# P-MT3620RDB-1-6_Dev.net
KiCad netlist of a schematic drawn in Altium Designer
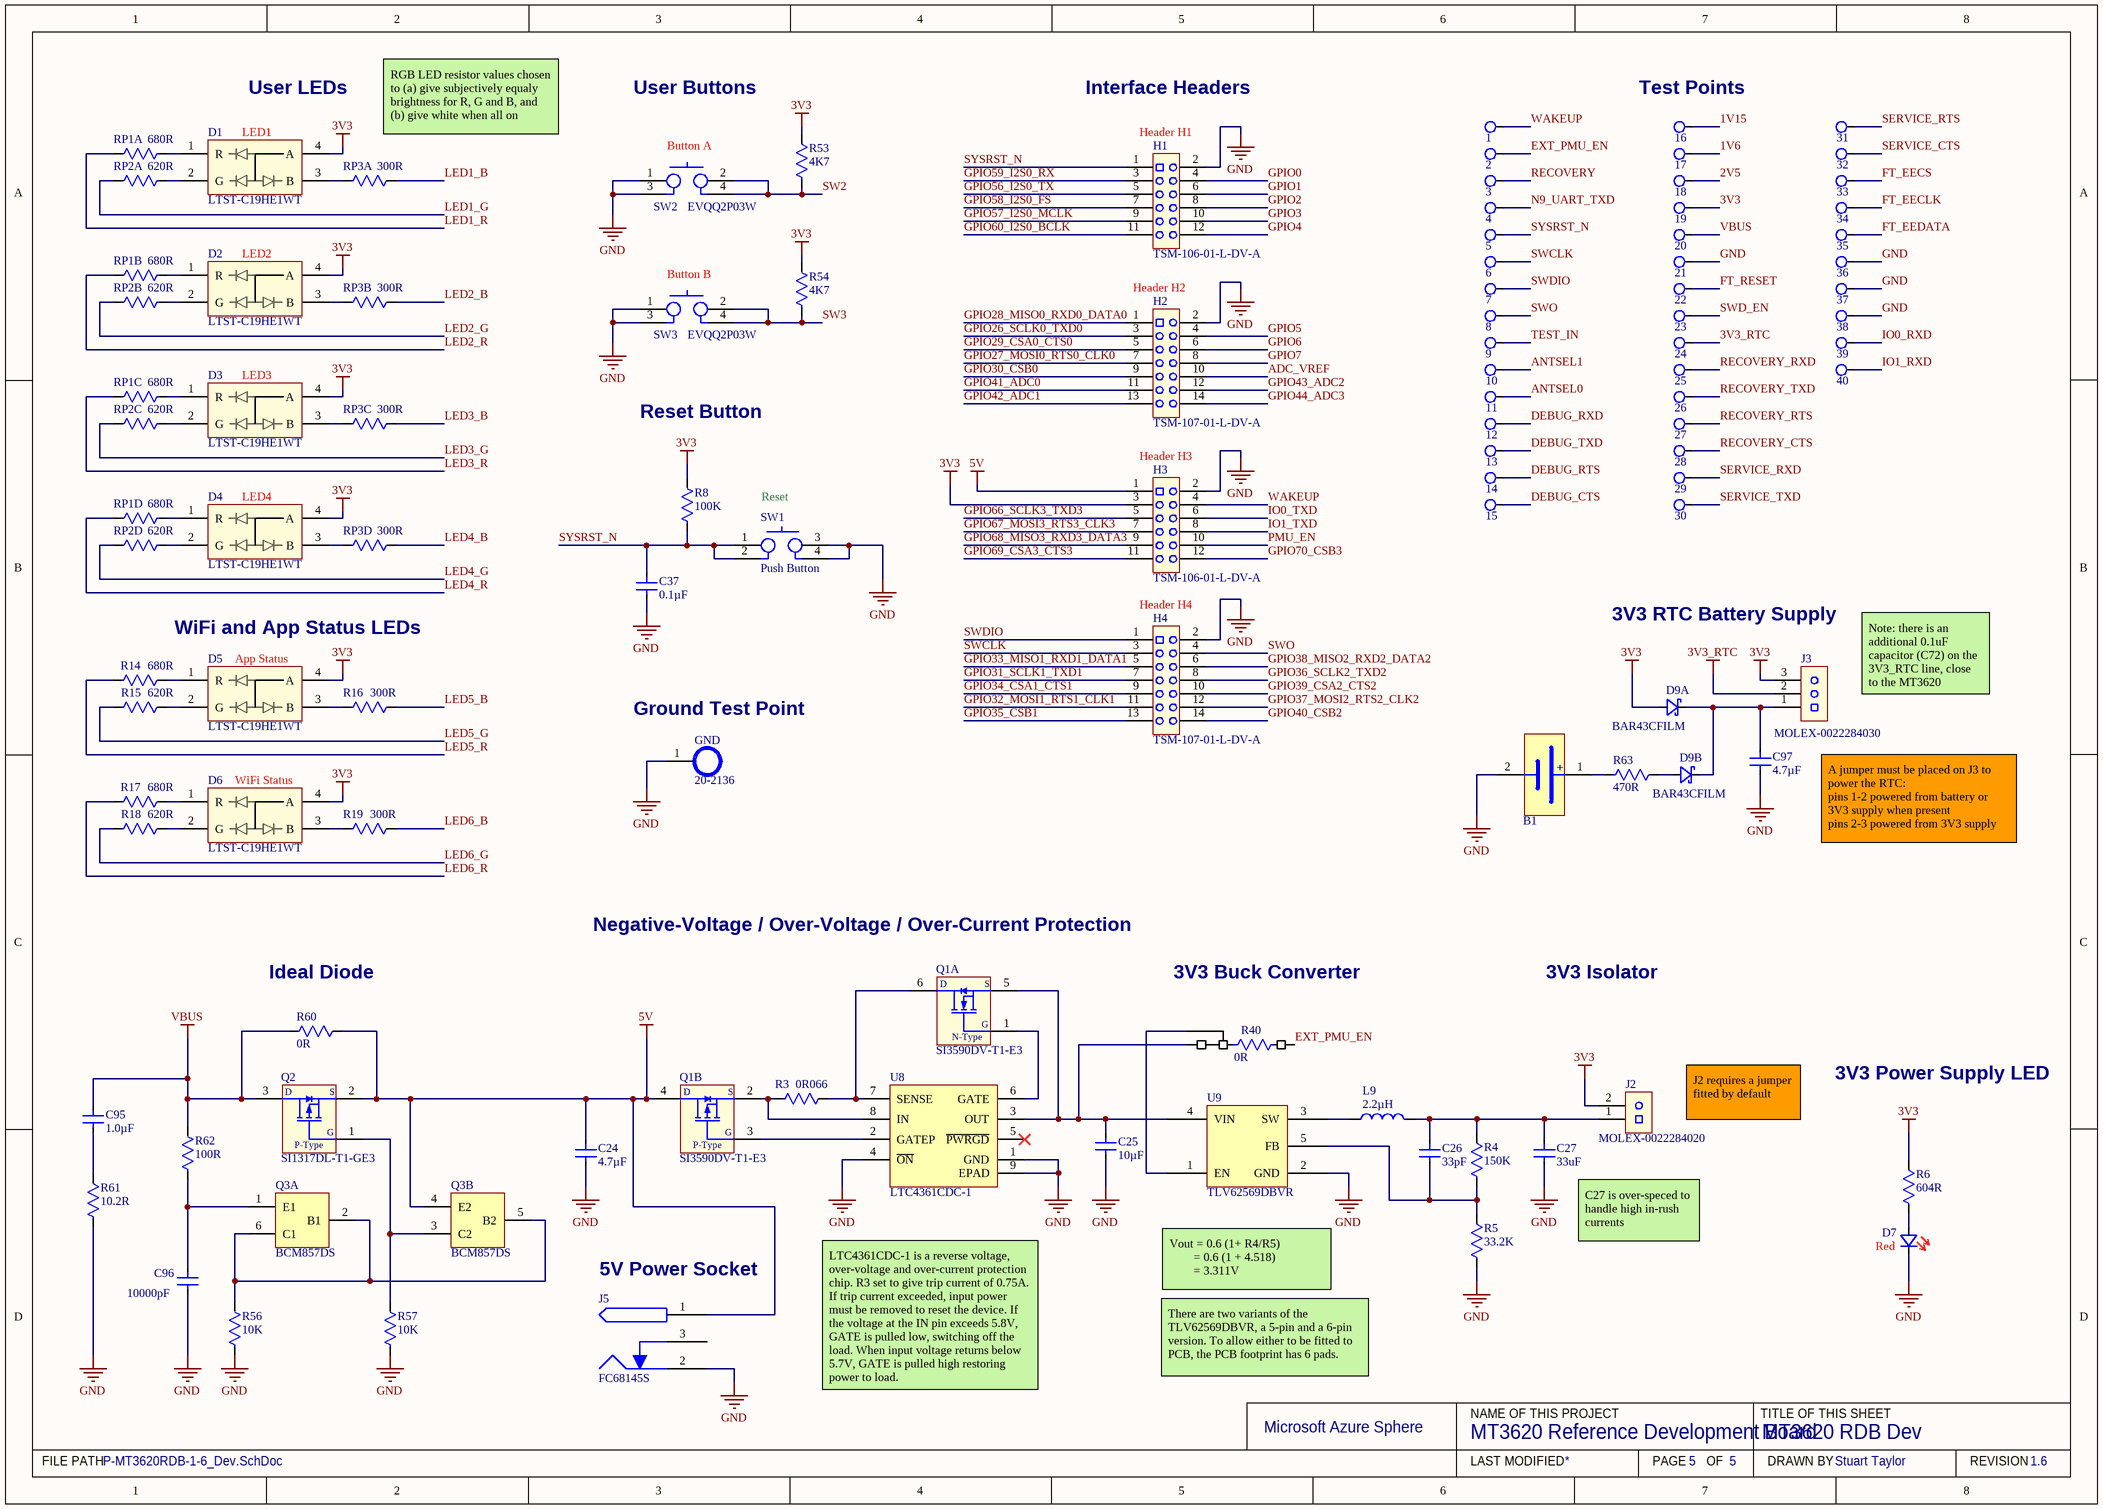
[diagram p0: P-MT3620RDB-1-6_Dev.SchDoc]

(export (version "E")
  (design (tool "Eeschema 10.0.6"))
  (components
    (comp (ref "1")
      (value "TestPoint")
      (footprint "Pad1.27mm")
      (description "Test Point")
      (libsource (lib "generic") (part "TestPoint"))
    )
    (comp (ref "2")
      (value "TestPoint")
      (footprint "Pad1.27mm")
      (description "Test Point")
      (libsource (lib "generic") (part "TestPoint"))
    )
    (comp (ref "3")
      (value "TestPoint")
      (footprint "Pad1.27mm")
      (description "Test Point")
      (libsource (lib "generic") (part "TestPoint"))
    )
    (comp (ref "4")
      (value "TestPoint")
      (footprint "Pad1.27mm")
      (description "Test Point")
      (libsource (lib "generic") (part "TestPoint"))
    )
    (comp (ref "5")
      (value "TestPoint")
      (footprint "Pad1.27mm")
      (description "Test Point")
      (libsource (lib "generic") (part "TestPoint"))
    )
    (comp (ref "6")
      (value "TestPoint")
      (footprint "Pad1.27mm")
      (description "Test Point")
      (libsource (lib "generic") (part "TestPoint"))
    )
    (comp (ref "7")
      (value "TestPoint")
      (footprint "Pad1.27mm")
      (description "Test Point")
      (libsource (lib "generic") (part "TestPoint"))
    )
    (comp (ref "8")
      (value "TestPoint")
      (footprint "Pad1.27mm")
      (description "Test Point")
      (libsource (lib "generic") (part "TestPoint"))
    )
    (comp (ref "9")
      (value "TestPoint")
      (footprint "Pad1.27mm")
      (description "Test Point")
      (libsource (lib "generic") (part "TestPoint"))
    )
    (comp (ref "10")
      (value "TestPoint")
      (footprint "Pad1.27mm")
      (description "Test Point")
      (libsource (lib "generic") (part "TestPoint"))
    )
    (comp (ref "11")
      (value "TestPoint")
      (footprint "Pad1.27mm")
      (description "Test Point")
      (libsource (lib "generic") (part "TestPoint"))
    )
    (comp (ref "12")
      (value "TestPoint")
      (footprint "Pad1.27mm")
      (description "Test Point")
      (libsource (lib "generic") (part "TestPoint"))
    )
    (comp (ref "13")
      (value "TestPoint")
      (footprint "Pad1.27mm")
      (description "Test Point")
      (libsource (lib "generic") (part "TestPoint"))
    )
    (comp (ref "14")
      (value "TestPoint")
      (footprint "Pad1.27mm")
      (description "Test Point")
      (libsource (lib "generic") (part "TestPoint"))
    )
    (comp (ref "15")
      (value "TestPoint")
      (footprint "Pad1.27mm")
      (description "Test Point")
      (libsource (lib "generic") (part "TestPoint"))
    )
    (comp (ref "16")
      (value "TestPoint")
      (footprint "Pad1.27mm")
      (description "Test Point")
      (libsource (lib "generic") (part "TestPoint"))
    )
    (comp (ref "17")
      (value "TestPoint")
      (footprint "Pad1.27mm")
      (description "Test Point")
      (libsource (lib "generic") (part "TestPoint"))
    )
    (comp (ref "18")
      (value "TestPoint")
      (footprint "Pad1.27mm")
      (description "Test Point")
      (libsource (lib "generic") (part "TestPoint"))
    )
    (comp (ref "19")
      (value "TestPoint")
      (footprint "Pad1.27mm")
      (description "Test Point")
      (libsource (lib "generic") (part "TestPoint"))
    )
    (comp (ref "20")
      (value "TestPoint")
      (footprint "Pad1.27mm")
      (description "Test Point")
      (libsource (lib "generic") (part "TestPoint"))
    )
    (comp (ref "21")
      (value "TestPoint")
      (footprint "Pad1.27mm")
      (description "Test Point")
      (libsource (lib "generic") (part "TestPoint"))
    )
    (comp (ref "22")
      (value "TestPoint")
      (footprint "Pad1.27mm")
      (description "Test Point")
      (libsource (lib "generic") (part "TestPoint"))
    )
    (comp (ref "23")
      (value "TestPoint")
      (footprint "Pad1.27mm")
      (description "Test Point")
      (libsource (lib "generic") (part "TestPoint"))
    )
    (comp (ref "24")
      (value "TestPoint")
      (footprint "Pad1.27mm")
      (description "Test Point")
      (libsource (lib "generic") (part "TestPoint"))
    )
    (comp (ref "25")
      (value "TestPoint")
      (footprint "Pad1.27mm")
      (description "Test Point")
      (libsource (lib "generic") (part "TestPoint"))
    )
    (comp (ref "26")
      (value "TestPoint")
      (footprint "Pad1.27mm")
      (description "Test Point")
      (libsource (lib "generic") (part "TestPoint"))
    )
    (comp (ref "27")
      (value "TestPoint")
      (footprint "Pad1.27mm")
      (description "Test Point")
      (libsource (lib "generic") (part "TestPoint"))
    )
    (comp (ref "28")
      (value "TestPoint")
      (footprint "Pad1.27mm")
      (description "Test Point")
      (libsource (lib "generic") (part "TestPoint"))
    )
    (comp (ref "29")
      (value "TestPoint")
      (footprint "Pad1.27mm")
      (description "Test Point")
      (libsource (lib "generic") (part "TestPoint"))
    )
    (comp (ref "30")
      (value "TestPoint")
      (footprint "Pad1.27mm")
      (description "Test Point")
      (libsource (lib "generic") (part "TestPoint"))
    )
    (comp (ref "31")
      (value "TestPoint")
      (footprint "Pad1.27mm")
      (description "Test Point")
      (libsource (lib "generic") (part "TestPoint"))
    )
    (comp (ref "32")
      (value "TestPoint")
      (footprint "Pad1.27mm")
      (description "Test Point")
      (libsource (lib "generic") (part "TestPoint"))
    )
    (comp (ref "33")
      (value "TestPoint")
      (footprint "Pad1.27mm")
      (description "Test Point")
      (libsource (lib "generic") (part "TestPoint"))
    )
    (comp (ref "34")
      (value "TestPoint")
      (footprint "Pad1.27mm")
      (description "Test Point")
      (libsource (lib "generic") (part "TestPoint"))
    )
    (comp (ref "35")
      (value "TestPoint")
      (footprint "Pad1.27mm")
      (description "Test Point")
      (libsource (lib "generic") (part "TestPoint"))
    )
    (comp (ref "36")
      (value "TestPoint")
      (footprint "Pad1.27mm")
      (description "Test Point")
      (libsource (lib "generic") (part "TestPoint"))
    )
    (comp (ref "37")
      (value "TestPoint")
      (footprint "Pad1.27mm")
      (description "Test Point")
      (libsource (lib "generic") (part "TestPoint"))
    )
    (comp (ref "38")
      (value "TestPoint")
      (footprint "Pad1.27mm")
      (description "Test Point")
      (libsource (lib "generic") (part "TestPoint"))
    )
    (comp (ref "39")
      (value "TestPoint")
      (footprint "Pad1.27mm")
      (description "Test Point")
      (libsource (lib "generic") (part "TestPoint"))
    )
    (comp (ref "40")
      (value "TestPoint")
      (footprint "Pad1.27mm")
      (description "Test Point")
      (libsource (lib "generic") (part "TestPoint"))
    )
    (comp (ref "B1")
      (value "HARWIN-S8421-45R")
      (footprint "HARWIN-S8421-45R")
      (description "SMT CR2032 coin cell holder")
      (fields (field (name "MANUFACTURER") "HARWIN") (field (name "MANUFACTURER PART NUMBER") "S8421-45R"))
      (libsource (lib "Harwin") (part "HARWIN-S8421-45R"))
    )
    (comp (ref "C24")
      (value "4.7µF")
      (footprint "CAPC1005-EIA0402 0.55MM MED")
      (description "CAP CER 4.7UF 10V 10% X5R 0402")
      (fields
        (field (name "MANUFACTURER") "TDK Corporation")
        (field (name "MANUFACTURER PART NUMBER") "C1005X5R1A475K050BC")
        (field (name "CAPACITANCE") "4.7µF")
      )
      (libsource (lib "TDK_Capacitor_C_0402") (part "4.7µF 0402 X5R 10V"))
    )
    (comp (ref "C25")
      (value "10µF")
      (footprint "CAPC1608-EIA0603-1MM-MED")
      (description "CAP CER 10UF 25V 20% X5R 0603")
      (fields
        (field (name "MANUFACTURER") "TDK Corporation")
        (field (name "MANUFACTURER PART NUMBER") "C1608X5R1E106M080AC")
        (field (name "CAPACITANCE") "10µF")
      )
      (libsource (lib "TDK-Capacitor_C_0603") (part "10µF 0603 X5R 25V"))
    )
    (comp (ref "C26")
      (value "33pF")
      (footprint "CAPC1005-EIA0402 0.55MM MED")
      (description "CAP CER 33PF 50V 5% NP0 0402")
      (fields
        (field (name "MANUFACTURER") "TDK Corporation")
        (field (name "MANUFACTURER PART NUMBER") "C1005C0G1H330J050BA")
        (field (name "CAPACITANCE") "33pF")
      )
      (libsource (lib "TDK_Capacitor_C_0402") (part "33pF 0402 C0G, NP0 50V"))
    )
    (comp (ref "C27")
      (value "33uF")
      (footprint "TDK_0805")
      (description "CAP CER 33UF 6.3V X5R 0805")
      (fields
        (field (name "MANUFACTURER") "TDK")
        (field (name "MANUFACTURER PART NUMBER") "C2012X5R0J336M125AC")
      )
      (libsource (lib "TDK_Capacitor_C_0805") (part "33uF 0805 X5R 6.3V"))
    )
    (comp (ref "C37")
      (value "0.1µF")
      (footprint "CAPC1005-EIA0402 0.55MM MED")
      (description "CAP CER 0.1UF 50V 10% X7R 0402")
      (fields
        (field (name "MANUFACTURER") "TDK Corporation")
        (field (name "MANUFACTURER PART NUMBER") "C1005X7R1H104K050BB")
        (field (name "CAPACITANCE") "0.1µF")
      )
      (libsource (lib "TDK_Capacitor_C_0402") (part "0.1µF 0402 X7R 50V"))
    )
    (comp (ref "C95")
      (value "1.0µF")
      (footprint "CAPC1005-EIA0402 0.55MM MED")
      (description "CAP CER 1UF 35V 10% X5R 0402")
      (fields
        (field (name "MANUFACTURER") "TDK Corporation")
        (field (name "MANUFACTURER PART NUMBER") "C1005X5R1V105K050BC")
        (field (name "CAPACITANCE") "1.0µF")
      )
      (libsource (lib "TDK_Capacitor_C_0402") (part "1.0µF 0402 X5R 35V"))
    )
    (comp (ref "C96")
      (value "10000pF")
      (footprint "CAPC1005-EIA0402 0.55MM MED")
      (description "CAP CER 10000PF 50V 10% X7R 0402")
      (fields
        (field (name "MANUFACTURER") "TDK Corporation")
        (field (name "MANUFACTURER PART NUMBER") "C1005X7R1H103K050BB")
        (field (name "CAPACITANCE") "10000pF")
      )
      (libsource (lib "TDK_Capacitor_C_0402") (part "10000pF 0402 X7R 50V"))
    )
    (comp (ref "C97")
      (value "4.7µF")
      (footprint "CAPC1005-EIA0402 0.55MM MED")
      (description "CAP CER 4.7UF 10V 10% X5R 0402")
      (fields
        (field (name "MANUFACTURER") "TDK Corporation")
        (field (name "MANUFACTURER PART NUMBER") "C1005X5R1A475K050BC")
        (field (name "CAPACITANCE") "4.7µF")
      )
      (libsource (lib "TDK_Capacitor_C_0402") (part "4.7µF 0402 X5R 10V"))
    )
    (comp (ref "D1")
      (value "LTST-C19HE1WT")
      (footprint "LTST-C19HE1WT")
      (description "LED RGB DIFFUSED 0606 SMD")
      (fields (field (name "MANUFACTURER") "Lite-On Inc."))
      (libsource (lib "Lite-On") (part "LTST-C19HE1WT"))
    )
    (comp (ref "D2")
      (value "LTST-C19HE1WT")
      (footprint "LTST-C19HE1WT")
      (description "LED RGB DIFFUSED 0606 SMD")
      (fields (field (name "MANUFACTURER") "Lite-On Inc."))
      (libsource (lib "Lite-On") (part "LTST-C19HE1WT"))
    )
    (comp (ref "D3")
      (value "LTST-C19HE1WT")
      (footprint "LTST-C19HE1WT")
      (description "LED RGB DIFFUSED 0606 SMD")
      (fields (field (name "MANUFACTURER") "Lite-On Inc."))
      (libsource (lib "Lite-On") (part "LTST-C19HE1WT"))
    )
    (comp (ref "D4")
      (value "LTST-C19HE1WT")
      (footprint "LTST-C19HE1WT")
      (description "LED RGB DIFFUSED 0606 SMD")
      (fields (field (name "MANUFACTURER") "Lite-On Inc."))
      (libsource (lib "Lite-On") (part "LTST-C19HE1WT"))
    )
    (comp (ref "D5")
      (value "LTST-C19HE1WT")
      (footprint "LTST-C19HE1WT")
      (description "LED RGB DIFFUSED 0606 SMD")
      (fields (field (name "MANUFACTURER") "Lite-On Inc."))
      (libsource (lib "Lite-On") (part "LTST-C19HE1WT"))
    )
    (comp (ref "D6")
      (value "LTST-C19HE1WT")
      (footprint "LTST-C19HE1WT")
      (description "LED RGB DIFFUSED 0606 SMD")
      (fields (field (name "MANUFACTURER") "Lite-On Inc."))
      (libsource (lib "Lite-On") (part "LTST-C19HE1WT"))
    )
    (comp (ref "D7")
      (value "Red LED")
      (footprint "Rohm SML-D12 Red")
      (description "1.6 x 0.8 x 0.55mm (0603) LED 620nm Red")
      (fields
        (field (name "MANUFACTURER") "Rohm Semiconductor")
        (field (name "MANUFACTURER PART NUMBER") "SML-D12U8WT86")
        (field (name "COLOUR") "Red")
      )
      (libsource (lib "Rohm") (part "SML-D12U"))
    )
    (comp (ref "D9")
      (value "BAR43CFILM")
      (footprint "ON_SEMI-SOT23-3")
      (description "DIODE ARRAY SCHOTTKY 30V SOT23-3")
      (fields (field (name "MANUFACTURER") "STMicroelectronics"))
      (libsource (lib "ST") (part "BAR43CFILM"))
    )
    (comp (ref "GND")
      (value "20-2136")
      (footprint "20-2136")
      (description "VERO - 20-2136 - TERMINAL, PCB, BLACK, PK100")
      (fields (field (name "MANUFACTURER") "VERO"))
      (libsource (lib "Vero") (part "20-2136"))
    )
    (comp (ref "H1")
      (value "TSM-106-01-L-DV-A")
      (footprint "TSM-106-01-L-DV-A")
      (description "CONN HEADER 12POS .100\" SMD GOLD")
      (fields (field (name "MANUFACTURER") "Samtec"))
      (libsource (lib "Samtec") (part "TSM-106-01-L-DV-A"))
    )
    (comp (ref "H2")
      (value "TSM-107-01-L-DV-A")
      (footprint "TSM-107-01-L-DV-A")
      (description "CONN HEADER 14POS .100\" SMD GOLD")
      (fields (field (name "MANUFACTURER") "Samtec"))
      (libsource (lib "Samtec") (part "TSM-107-01-L-DV-A"))
    )
    (comp (ref "H3")
      (value "TSM-106-01-L-DV-A")
      (footprint "TSM-106-01-L-DV-A")
      (description "CONN HEADER 12POS .100\" SMD GOLD")
      (fields (field (name "MANUFACTURER") "Samtec"))
      (libsource (lib "Samtec") (part "TSM-106-01-L-DV-A"))
    )
    (comp (ref "H4")
      (value "TSM-107-01-L-DV-A")
      (footprint "TSM-107-01-L-DV-A")
      (description "CONN HEADER 14POS .100\" SMD GOLD")
      (fields (field (name "MANUFACTURER") "Samtec"))
      (libsource (lib "Samtec") (part "TSM-107-01-L-DV-A"))
    )
    (comp (ref "J2")
      (value "MOLEX-0022284020")
      (footprint "0022284020")
      (description "CONN HEADER 2POS .100 VERT TIN")
      (fields
        (field (name "MANUFACTURER") "Molex, LLC")
        (field (name "MANUFACTURER PART NUMBER") "0022284020")
      )
      (libsource (lib "Molex") (part "MOLEX-0022284020"))
    )
    (comp (ref "J3")
      (value "MOLEX-0022284030")
      (footprint "0022284030")
      (description "CONN HEADER 3POS .100 VERT TIN")
      (fields
        (field (name "MANUFACTURER") "Molex, LLC")
        (field (name "MANUFACTURER PART NUMBER") "0022284030")
      )
      (libsource (lib "Molex") (part "MOLEX-0022284030"))
    )
    (comp (ref "J5")
      (value "FC68145S")
      (footprint "FC68145S")
      (description "CLIFF ELECTRONIC COMPONENTS, FC68145S, DC Power Connector, Jack, 1 A, 1.3 mm, Surface Mount")
      (fields (field (name "MANUFACTURER") "Cliff"))
      (libsource (lib "Cliff") (part "FC68145S"))
    )
    (comp (ref "L9")
      (value "2.2µH")
      (footprint "NR3015T2R2M")
      (description "FIXED IND 2.2UH 1.5A 72 MOHM SMD")
      (fields
        (field (name "MANUFACTURER") "Taiyo Yuden")
        (field (name "MANUFACTURER PART NUMBER") "NR3015T2R2M")
      )
      (libsource (lib "TaiyoYuden ") (part "NR3015T2R2M"))
    )
    (comp (ref "Q1")
      (value "SI3590DV-T1-E3")
      (footprint "SI3590DV-T1-E3")
      (description "MOSFET N&P-CH 30V (D-S)")
      (fields (field (name "MANUFACTURER") "Vishay Siliconix"))
      (libsource (lib "Vishay") (part "SI3590DV-T1-E3"))
    )
    (comp (ref "Q2")
      (value "SI1317DL-T1-GE3")
      (footprint "VISHAY_SOT-323")
      (description "VISHAY SI1317DL-T1-GE3 MOSFET Transistor, P Channel, -1.4 A, -20 V, 0.125 ohm, -4.5 V, 450 mV")
      (fields (field (name "MANUFACTURER") "Vishay Siliconix"))
      (libsource (lib "Vishay") (part "SI1317DL-T1-GE3"))
    )
    (comp (ref "Q3")
      (value "BCM857DS")
      (footprint "NXP-SOT457")
      (description "BJT ARRAY, DUAL PNP, -45V, -100MA, 6-SOT-457")
      (fields
        (field (name "MANUFACTURER") "NXP Semiconductors")
        (field (name "MANUFACTURER PART NUMBER") "BCM857DS,115")
      )
      (libsource (lib "NXP") (part "BCM857DS,115"))
    )
    (comp (ref "R3")
      (value "0R066")
      (footprint "VISHAY-0603")
      (description "Current Sense Resistors - SMD .4watt .066ohm 1%")
      (fields
        (field (name "MANUFACTURER") "Vishay Dale")
        (field (name "MANUFACTURER PART NUMBER") "WSLP0603R0660FEB")
      )
      (libsource (lib "Vishay") (part "WSLP0603R0660FEB"))
    )
    (comp (ref "R4")
      (value "150K")
      (footprint "RES 0402 MEDIUM DENSITY")
      (description "RES 150K OHM 1/10W 1% 0402 SMD")
      (fields
        (field (name "MANUFACTURER") "Panasonic Electronic Components")
        (field (name "MANUFACTURER PART NUMBER") "ERJ-2RKF1503X")
        (field (name "RESISTANCE (OHMS)") "150K")
      )
      (libsource (lib "Panasonic_Resistor_ERJ2R") (part "150K"))
    )
    (comp (ref "R5")
      (value "33.2K")
      (footprint "RES 0402 MEDIUM DENSITY")
      (description "RES 33.2K OHM 1/10W 1% 0402 SMD")
      (fields
        (field (name "MANUFACTURER") "Panasonic Electronic Components")
        (field (name "MANUFACTURER PART NUMBER") "ERJ-2RKF3322X")
        (field (name "RESISTANCE (OHMS)") "33.2K")
      )
      (libsource (lib "Panasonic_Resistor_ERJ2R") (part "33.2K"))
    )
    (comp (ref "R6")
      (value "604R")
      (footprint "RES 0402 MEDIUM DENSITY")
      (description "RES 604 OHM 1/10W 1% 0402 SMD")
      (fields
        (field (name "MANUFACTURER") "Panasonic Electronic Components")
        (field (name "MANUFACTURER PART NUMBER") "ERJ-2RKF6040X")
        (field (name "RESISTANCE (OHMS)") "604R")
      )
      (libsource (lib "Panasonic_Resistor_ERJ2R") (part "604R"))
    )
    (comp (ref "R8")
      (value "100K")
      (footprint "RES 0402 MEDIUM DENSITY")
      (description "RES 100K OHM 1/10W 1% 0402 SMD")
      (fields
        (field (name "MANUFACTURER") "Panasonic Electronic Components")
        (field (name "MANUFACTURER PART NUMBER") "ERJ-2RKF1003X")
        (field (name "RESISTANCE (OHMS)") "100K")
      )
      (libsource (lib "Panasonic_Resistor_ERJ2R") (part "100K"))
    )
    (comp (ref "R14")
      (value "680R")
      (footprint "RES 0402 MEDIUM DENSITY")
      (description "RES 680 OHM 1/10W 1% 0402 SMD")
      (fields
        (field (name "MANUFACTURER") "Panasonic Electronic Components")
        (field (name "MANUFACTURER PART NUMBER") "ERJ-2RKF6800X")
        (field (name "RESISTANCE (OHMS)") "680R")
      )
      (libsource (lib "Panasonic_Resistor_ERJ2R") (part "680R"))
    )
    (comp (ref "R15")
      (value "620R")
      (footprint "RES 0402 MEDIUM DENSITY")
      (description "RES 620 OHM 1/10W 1% 0402 SMD")
      (fields
        (field (name "MANUFACTURER") "Panasonic Electronic Components")
        (field (name "MANUFACTURER PART NUMBER") "ERJ-2RKF6200X")
        (field (name "RESISTANCE (OHMS)") "620R")
      )
      (libsource (lib "Panasonic_Resistor_ERJ2R") (part "620R"))
    )
    (comp (ref "R16")
      (value "300R")
      (footprint "RES 0402 MEDIUM DENSITY")
      (description "RES 300 OHM 1/10W 1% 0402 SMD")
      (fields
        (field (name "MANUFACTURER") "Panasonic Electronic Components")
        (field (name "MANUFACTURER PART NUMBER") "ERJ-2RKF3000X")
        (field (name "RESISTANCE (OHMS)") "300R")
      )
      (libsource (lib "Panasonic_Resistor_ERJ2R") (part "300R"))
    )
    (comp (ref "R17")
      (value "680R")
      (footprint "RES 0402 MEDIUM DENSITY")
      (description "RES 680 OHM 1/10W 1% 0402 SMD")
      (fields
        (field (name "MANUFACTURER") "Panasonic Electronic Components")
        (field (name "MANUFACTURER PART NUMBER") "ERJ-2RKF6800X")
        (field (name "RESISTANCE (OHMS)") "680R")
      )
      (libsource (lib "Panasonic_Resistor_ERJ2R") (part "680R"))
    )
    (comp (ref "R18")
      (value "620R")
      (footprint "RES 0402 MEDIUM DENSITY")
      (description "RES 620 OHM 1/10W 1% 0402 SMD")
      (fields
        (field (name "MANUFACTURER") "Panasonic Electronic Components")
        (field (name "MANUFACTURER PART NUMBER") "ERJ-2RKF6200X")
        (field (name "RESISTANCE (OHMS)") "620R")
      )
      (libsource (lib "Panasonic_Resistor_ERJ2R") (part "620R"))
    )
    (comp (ref "R19")
      (value "300R")
      (footprint "RES 0402 MEDIUM DENSITY")
      (description "RES 300 OHM 1/10W 1% 0402 SMD")
      (fields
        (field (name "MANUFACTURER") "Panasonic Electronic Components")
        (field (name "MANUFACTURER PART NUMBER") "ERJ-2RKF3000X")
        (field (name "RESISTANCE (OHMS)") "300R")
      )
      (libsource (lib "Panasonic_Resistor_ERJ2R") (part "300R"))
    )
    (comp (ref "R40")
      (value "0R")
      (footprint "THREE-WAY-0402-WITH-SHORT")
      (description "RES SMD 0.0OHM JUMPER 1/10W 0402")
      (fields
        (field (name "MANUFACTURER") "Panasonic Electronic Components")
        (field (name "MANUFACTURER PART NUMBER") "ERJ-2GE0R00X")
      )
      (libsource (lib "generic-res") (part "THREE-WAY-0R-0402"))
    )
    (comp (ref "R53")
      (value "4K7")
      (footprint "RES 0402 MEDIUM DENSITY")
      (description "RES 4.7K OHM 1/10W 1% 0402 SMD")
      (fields
        (field (name "MANUFACTURER") "Panasonic Electronic Components")
        (field (name "MANUFACTURER PART NUMBER") "ERJ-2RKF4701X")
        (field (name "RESISTANCE (OHMS)") "4K7")
      )
      (libsource (lib "Panasonic_Resistor_ERJ2R") (part "4.7K"))
    )
    (comp (ref "R54")
      (value "4K7")
      (footprint "RES 0402 MEDIUM DENSITY")
      (description "RES 4.7K OHM 1/10W 1% 0402 SMD")
      (fields
        (field (name "MANUFACTURER") "Panasonic Electronic Components")
        (field (name "MANUFACTURER PART NUMBER") "ERJ-2RKF4701X")
        (field (name "RESISTANCE (OHMS)") "4K7")
      )
      (libsource (lib "Panasonic_Resistor_ERJ2R") (part "4.7K"))
    )
    (comp (ref "R56")
      (value "10K")
      (footprint "RES 0402 MEDIUM DENSITY")
      (description "RES 10K OHM 1/10W 1% 0402 SMD")
      (fields
        (field (name "MANUFACTURER") "Panasonic Electronic Components")
        (field (name "MANUFACTURER PART NUMBER") "ERJ-2RKF1002X")
        (field (name "RESISTANCE (OHMS)") "10K")
      )
      (libsource (lib "Panasonic_Resistor_ERJ2R") (part "10K"))
    )
    (comp (ref "R57")
      (value "10K")
      (footprint "RES 0402 MEDIUM DENSITY")
      (description "RES 10K OHM 1/10W 1% 0402 SMD")
      (fields
        (field (name "MANUFACTURER") "Panasonic Electronic Components")
        (field (name "MANUFACTURER PART NUMBER") "ERJ-2RKF1002X")
        (field (name "RESISTANCE (OHMS)") "10K")
      )
      (libsource (lib "Panasonic_Resistor_ERJ2R") (part "10K"))
    )
    (comp (ref "R60")
      (value "0R")
      (footprint "RES 0402 MEDIUM DENSITY")
      (description "RES 0.0 OHM 1/10W JUMP 0402 SMD")
      (fields
        (field (name "MANUFACTURER") "Panasonic Electronic Components")
        (field (name "MANUFACTURER PART NUMBER") "ERJ-2GE0R00X")
        (field (name "RESISTANCE (OHMS)") "0R")
      )
      (libsource (lib "Panasonic_Resistor_ERJ2R") (part "0R"))
    )
    (comp (ref "R61")
      (value "10.2R")
      (footprint "RES 0402 MEDIUM DENSITY")
      (description "RES 10.2 OHM 1/10W 1% 0402 SMD")
      (fields
        (field (name "MANUFACTURER") "Panasonic Electronic Components")
        (field (name "MANUFACTURER PART NUMBER") "ERJ-2RKF10R2X")
        (field (name "RESISTANCE (OHMS)") "10.2R")
      )
      (libsource (lib "Panasonic_Resistor_ERJ2R") (part "10.2R"))
    )
    (comp (ref "R62")
      (value "100R")
      (footprint "RES 0402 MEDIUM DENSITY")
      (description "RES 100 OHM 1/10W 1% 0402 SMD")
      (fields
        (field (name "MANUFACTURER") "Panasonic Electronic Components")
        (field (name "MANUFACTURER PART NUMBER") "ERJ-2RKF1000X")
        (field (name "RESISTANCE (OHMS)") "100R")
      )
      (libsource (lib "Panasonic_Resistor_ERJ2R") (part "100R"))
    )
    (comp (ref "R63")
      (value "470R")
      (footprint "RES 0402 MEDIUM DENSITY")
      (description "RES 470 OHM 1/10W 1% 0402 SMD")
      (fields
        (field (name "MANUFACTURER") "Panasonic Electronic Components")
        (field (name "MANUFACTURER PART NUMBER") "ERJ-2RKF4700X")
        (field (name "RESISTANCE (OHMS)") "470R")
      )
      (libsource (lib "Panasonic_Resistor_ERJ2R") (part "470R"))
    )
    (comp (ref "RP1")
      (value "680R")
      (footprint "EXB-N8V")
      (fields
        (field (name "MANUFACTURER") "Panasonic / Panasonic ECG")
        (field (name "MANUFACTURER PART NUMBER") "EXB-N8V681JX")
      )
      (libsource (lib "Panasonic") (part "EXB-N8V681JX"))
    )
    (comp (ref "RP2")
      (value "620R")
      (footprint "EXB-N8V")
      (fields
        (field (name "MANUFACTURER") "Panasonic ECG")
        (field (name "MANUFACTURER PART NUMBER") "EXB-N8V621JX")
        (field (name "TOLERANCE") "5%")
      )
      (libsource (lib "Panasonic") (part "EXB-N8V621JX"))
    )
    (comp (ref "RP3")
      (value "300R")
      (footprint "EXB-N8V")
      (fields
        (field (name "MANUFACTURER") "Panasonic / Panasonic ECG")
        (field (name "MANUFACTURER PART NUMBER") "EXB-N8V301JX")
        (field (name "TOLERANCE") "5%")
      )
      (libsource (lib "Panasonic") (part "EXB-N8V301JX"))
    )
    (comp (ref "SW1")
      (value "Push Button")
      (footprint "DHT-1158")
      (libsource (lib "Seeed") (part "DHT-1158"))
    )
    (comp (ref "SW2")
      (value "SWI TACT SPN0 PANASONIC EVQQ2P03W")
      (footprint "EVQQ2P03W")
      (description "PANASONIC - EVQQ2P03W - SWITCH, SPNO, SMD")
      (fields (field (name "MANUFACTURER") "PANASONIC") (field (name "MANUFACTURER PART NUMBER") "EVQQ2P03W"))
      (libsource (lib "switch") (part "SWI TACT SPN0 PANASONIC EVQQ2P03W"))
    )
    (comp (ref "SW3")
      (value "SWI TACT SPN0 PANASONIC EVQQ2P03W")
      (footprint "EVQQ2P03W")
      (description "PANASONIC - EVQQ2P03W - SWITCH, SPNO, SMD")
      (fields (field (name "MANUFACTURER") "PANASONIC") (field (name "MANUFACTURER PART NUMBER") "EVQQ2P03W"))
      (libsource (lib "switch") (part "SWI TACT SPN0 PANASONIC EVQQ2P03W"))
    )
    (comp (ref "U8")
      (value "LTC4361CDC-1")
      (footprint "LTC4361-1#TRPBF")
      (description "LINEAR TECHNOLOGY LTC4361CDC-1#TRMPBF IC, OVERVOLTAGE/CUR PROT, 8DFN")
      (fields
        (field (name "MANUFACTURER") "Linear Technology")
        (field (name "MANUFACTURER PART NUMBER") "LTC4361CDC-1#TRMPBF")
      )
      (libsource (lib "LinearTech") (part "LTC4361CDC-1#TRMPBF"))
    )
    (comp (ref "U9")
      (value "TLV62569DBVR")
      (footprint "TI-SOT23-6")
      (description "Variable voltage buck converter")
      (fields (field (name "MANUFACTURER") "Texas Instruments"))
      (libsource (lib "TexasInstruments") (part "TLV62569DBVR"))
    )
  )
  (nets
    (net (code "1") (name "/1V6") (class "Default")
      (node (ref "17") (pin "1") (pinfunction "1_1") (pintype "passive"))
    )
    (net (code "2") (name "/1V15") (class "Default")
      (node (ref "16") (pin "1") (pinfunction "1_1") (pintype "passive"))
    )
    (net (code "3") (name "/2V5") (class "Default")
      (node (ref "18") (pin "1") (pinfunction "1_1") (pintype "passive"))
    )
    (net (code "4") (name "/ADC_VREF") (class "Default")
      (node (ref "H2") (pin "10") (pinfunction "10_10") (pintype "passive"))
    )
    (net (code "5") (name "/ANTSEL0") (class "Default")
      (node (ref "11") (pin "1") (pinfunction "1_1") (pintype "passive"))
    )
    (net (code "6") (name "/ANTSEL1") (class "Default")
      (node (ref "10") (pin "1") (pinfunction "1_1") (pintype "passive"))
    )
    (net (code "7") (name "/DEBUG_CTS") (class "Default")
      (node (ref "15") (pin "1") (pinfunction "1_1") (pintype "passive"))
    )
    (net (code "8") (name "/DEBUG_RTS") (class "Default")
      (node (ref "14") (pin "1") (pinfunction "1_1") (pintype "passive"))
    )
    (net (code "9") (name "/DEBUG_RXD") (class "Default")
      (node (ref "12") (pin "1") (pinfunction "1_1") (pintype "passive"))
    )
    (net (code "10") (name "/DEBUG_TXD") (class "Default")
      (node (ref "13") (pin "1") (pinfunction "1_1") (pintype "passive"))
    )
    (net (code "11") (name "/EXT_PMU_EN") (class "Default")
      (node (ref "2") (pin "1") (pinfunction "1_1") (pintype "passive"))
      (node (ref "R40") (pin "1") (pinfunction "1_1") (pintype "passive"))
    )
    (net (code "12") (name "/FT_EECLK") (class "Default")
      (node (ref "34") (pin "1") (pinfunction "1_1") (pintype "passive"))
    )
    (net (code "13") (name "/FT_EECS") (class "Default")
      (node (ref "33") (pin "1") (pinfunction "1_1") (pintype "passive"))
    )
    (net (code "14") (name "/FT_EEDATA") (class "Default")
      (node (ref "35") (pin "1") (pinfunction "1_1") (pintype "passive"))
    )
    (net (code "15") (name "/FT_RESET") (class "Default")
      (node (ref "22") (pin "1") (pinfunction "1_1") (pintype "passive"))
    )
    (net (code "16") (name "/GPIO0") (class "Default")
      (node (ref "H1") (pin "4") (pinfunction "4_4") (pintype "passive"))
    )
    (net (code "17") (name "/GPIO1") (class "Default")
      (node (ref "H1") (pin "6") (pinfunction "6_6") (pintype "passive"))
    )
    (net (code "18") (name "/GPIO2") (class "Default")
      (node (ref "H1") (pin "8") (pinfunction "8_8") (pintype "passive"))
    )
    (net (code "19") (name "/GPIO3") (class "Default")
      (node (ref "H1") (pin "10") (pinfunction "10_10") (pintype "passive"))
    )
    (net (code "20") (name "/GPIO4") (class "Default")
      (node (ref "H1") (pin "12") (pinfunction "12_12") (pintype "passive"))
    )
    (net (code "21") (name "/GPIO5") (class "Default")
      (node (ref "H2") (pin "4") (pinfunction "4_4") (pintype "passive"))
    )
    (net (code "22") (name "/GPIO6") (class "Default")
      (node (ref "H2") (pin "6") (pinfunction "6_6") (pintype "passive"))
    )
    (net (code "23") (name "/GPIO7") (class "Default")
      (node (ref "H2") (pin "8") (pinfunction "8_8") (pintype "passive"))
    )
    (net (code "24") (name "/GPIO26_SCLK0_TXD0") (class "Default")
      (node (ref "H2") (pin "3") (pinfunction "3_3") (pintype "passive"))
    )
    (net (code "25") (name "/GPIO27_MOSI0_RTS0_CLK0") (class "Default")
      (node (ref "H2") (pin "7") (pinfunction "7_7") (pintype "passive"))
    )
    (net (code "26") (name "/GPIO28_MISO0_RXD0_DATA0") (class "Default")
      (node (ref "H2") (pin "1") (pinfunction "1_1") (pintype "passive"))
    )
    (net (code "27") (name "/GPIO29_CSA0_CTS0") (class "Default")
      (node (ref "H2") (pin "5") (pinfunction "5_5") (pintype "passive"))
    )
    (net (code "28") (name "/GPIO30_CSB0") (class "Default")
      (node (ref "H2") (pin "9") (pinfunction "9_9") (pintype "passive"))
    )
    (net (code "29") (name "/GPIO31_SCLK1_TXD1") (class "Default")
      (node (ref "H4") (pin "7") (pinfunction "7_7") (pintype "passive"))
    )
    (net (code "30") (name "/GPIO32_MOSI1_RTS1_CLK1") (class "Default")
      (node (ref "H4") (pin "11") (pinfunction "11_11") (pintype "passive"))
    )
    (net (code "31") (name "/GPIO33_MISO1_RXD1_DATA1") (class "Default")
      (node (ref "H4") (pin "5") (pinfunction "5_5") (pintype "passive"))
    )
    (net (code "32") (name "/GPIO34_CSA1_CTS1") (class "Default")
      (node (ref "H4") (pin "9") (pinfunction "9_9") (pintype "passive"))
    )
    (net (code "33") (name "/GPIO35_CSB1") (class "Default")
      (node (ref "H4") (pin "13") (pinfunction "13_13") (pintype "passive"))
    )
    (net (code "34") (name "/GPIO36_SCLK2_TXD2") (class "Default")
      (node (ref "H4") (pin "8") (pinfunction "8_8") (pintype "passive"))
    )
    (net (code "35") (name "/GPIO37_MOSI2_RTS2_CLK2") (class "Default")
      (node (ref "H4") (pin "12") (pinfunction "12_12") (pintype "passive"))
    )
    (net (code "36") (name "/GPIO38_MISO2_RXD2_DATA2") (class "Default")
      (node (ref "H4") (pin "6") (pinfunction "6_6") (pintype "passive"))
    )
    (net (code "37") (name "/GPIO39_CSA2_CTS2") (class "Default")
      (node (ref "H4") (pin "10") (pinfunction "10_10") (pintype "passive"))
    )
    (net (code "38") (name "/GPIO40_CSB2") (class "Default")
      (node (ref "H4") (pin "14") (pinfunction "14_14") (pintype "passive"))
    )
    (net (code "39") (name "/GPIO41_ADC0") (class "Default")
      (node (ref "H2") (pin "11") (pinfunction "11_11") (pintype "passive"))
    )
    (net (code "40") (name "/GPIO42_ADC1") (class "Default")
      (node (ref "H2") (pin "13") (pinfunction "13_13") (pintype "passive"))
    )
    (net (code "41") (name "/GPIO43_ADC2") (class "Default")
      (node (ref "H2") (pin "12") (pinfunction "12_12") (pintype "passive"))
    )
    (net (code "42") (name "/GPIO44_ADC3") (class "Default")
      (node (ref "H2") (pin "14") (pinfunction "14_14") (pintype "passive"))
    )
    (net (code "43") (name "/GPIO56_I2S0_TX") (class "Default")
      (node (ref "H1") (pin "5") (pinfunction "5_5") (pintype "passive"))
    )
    (net (code "44") (name "/GPIO57_I2S0_MCLK") (class "Default")
      (node (ref "H1") (pin "9") (pinfunction "9_9") (pintype "passive"))
    )
    (net (code "45") (name "/GPIO58_I2S0_FS") (class "Default")
      (node (ref "H1") (pin "7") (pinfunction "7_7") (pintype "passive"))
    )
    (net (code "46") (name "/GPIO59_I2S0_RX") (class "Default")
      (node (ref "H1") (pin "3") (pinfunction "3_3") (pintype "passive"))
    )
    (net (code "47") (name "/GPIO60_I2S0_BCLK") (class "Default")
      (node (ref "H1") (pin "11") (pinfunction "11_11") (pintype "passive"))
    )
    (net (code "48") (name "/GPIO66_SCLK3_TXD3") (class "Default")
      (node (ref "H3") (pin "5") (pinfunction "5_5") (pintype "passive"))
    )
    (net (code "49") (name "/GPIO67_MOSI3_RTS3_CLK3") (class "Default")
      (node (ref "H3") (pin "7") (pinfunction "7_7") (pintype "passive"))
    )
    (net (code "50") (name "/GPIO68_MISO3_RXD3_DATA3") (class "Default")
      (node (ref "H3") (pin "9") (pinfunction "9_9") (pintype "passive"))
    )
    (net (code "51") (name "/GPIO69_CSA3_CTS3") (class "Default")
      (node (ref "H3") (pin "11") (pinfunction "11_11") (pintype "passive"))
    )
    (net (code "52") (name "/GPIO70_CSB3") (class "Default")
      (node (ref "H3") (pin "12") (pinfunction "12_12") (pintype "passive"))
    )
    (net (code "53") (name "/IO0_RXD") (class "Default")
      (node (ref "39") (pin "1") (pinfunction "1_1") (pintype "passive"))
    )
    (net (code "54") (name "/IO0_TXD") (class "Default")
      (node (ref "H3") (pin "6") (pinfunction "6_6") (pintype "passive"))
    )
    (net (code "55") (name "/IO1_RXD") (class "Default")
      (node (ref "40") (pin "1") (pinfunction "1_1") (pintype "passive"))
    )
    (net (code "56") (name "/IO1_TXD") (class "Default")
      (node (ref "H3") (pin "8") (pinfunction "8_8") (pintype "passive"))
    )
    (net (code "57") (name "/LED1_B") (class "Default")
      (node (ref "RP3") (pin "2") (pinfunction "2_2") (pintype "passive"))
    )
    (net (code "58") (name "/LED1_G") (class "Default")
      (node (ref "RP2") (pin "2") (pinfunction "2_2") (pintype "passive"))
    )
    (net (code "59") (name "/LED1_R") (class "Default")
      (node (ref "RP1") (pin "2") (pinfunction "2_2") (pintype "passive"))
    )
    (net (code "60") (name "/LED2_B") (class "Default")
      (node (ref "RP3") (pin "4") (pinfunction "4_4") (pintype "passive"))
    )
    (net (code "61") (name "/LED2_G") (class "Default")
      (node (ref "RP2") (pin "4") (pinfunction "4_4") (pintype "passive"))
    )
    (net (code "62") (name "/LED2_R") (class "Default")
      (node (ref "RP1") (pin "4") (pinfunction "4_4") (pintype "passive"))
    )
    (net (code "63") (name "/LED3_B") (class "Default")
      (node (ref "RP3") (pin "6") (pinfunction "6_6") (pintype "passive"))
    )
    (net (code "64") (name "/LED3_G") (class "Default")
      (node (ref "RP2") (pin "6") (pinfunction "6_6") (pintype "passive"))
    )
    (net (code "65") (name "/LED3_R") (class "Default")
      (node (ref "RP1") (pin "6") (pinfunction "6_6") (pintype "passive"))
    )
    (net (code "66") (name "/LED4_B") (class "Default")
      (node (ref "RP3") (pin "8") (pinfunction "8_8") (pintype "passive"))
    )
    (net (code "67") (name "/LED4_G") (class "Default")
      (node (ref "RP2") (pin "8") (pinfunction "8_8") (pintype "passive"))
    )
    (net (code "68") (name "/LED4_R") (class "Default")
      (node (ref "RP1") (pin "8") (pinfunction "8_8") (pintype "passive"))
    )
    (net (code "69") (name "/LED5_B") (class "Default")
      (node (ref "R16") (pin "1") (pinfunction "1_1") (pintype "passive"))
    )
    (net (code "70") (name "/LED5_G") (class "Default")
      (node (ref "R15") (pin "2") (pinfunction "2_2") (pintype "passive"))
    )
    (net (code "71") (name "/LED5_R") (class "Default")
      (node (ref "R14") (pin "2") (pinfunction "2_2") (pintype "passive"))
    )
    (net (code "72") (name "/LED6_B") (class "Default")
      (node (ref "R19") (pin "1") (pinfunction "1_1") (pintype "passive"))
    )
    (net (code "73") (name "/LED6_G") (class "Default")
      (node (ref "R18") (pin "2") (pinfunction "2_2") (pintype "passive"))
    )
    (net (code "74") (name "/LED6_R") (class "Default")
      (node (ref "R17") (pin "2") (pinfunction "2_2") (pintype "passive"))
    )
    (net (code "75") (name "/N9_UART_TXD") (class "Default")
      (node (ref "4") (pin "1") (pinfunction "1_1") (pintype "passive"))
    )
    (net (code "76") (name "/PMU_EN") (class "Default")
      (node (ref "H3") (pin "10") (pinfunction "10_10") (pintype "passive"))
    )
    (net (code "77") (name "/RECOVERY") (class "Default")
      (node (ref "3") (pin "1") (pinfunction "1_1") (pintype "passive"))
    )
    (net (code "78") (name "/RECOVERY_CTS") (class "Default")
      (node (ref "28") (pin "1") (pinfunction "1_1") (pintype "passive"))
    )
    (net (code "79") (name "/RECOVERY_RTS") (class "Default")
      (node (ref "27") (pin "1") (pinfunction "1_1") (pintype "passive"))
    )
    (net (code "80") (name "/RECOVERY_RXD") (class "Default")
      (node (ref "25") (pin "1") (pinfunction "1_1") (pintype "passive"))
    )
    (net (code "81") (name "/RECOVERY_TXD") (class "Default")
      (node (ref "26") (pin "1") (pinfunction "1_1") (pintype "passive"))
    )
    (net (code "82") (name "/SERVICE_CTS") (class "Default")
      (node (ref "32") (pin "1") (pinfunction "1_1") (pintype "passive"))
    )
    (net (code "83") (name "/SERVICE_RTS") (class "Default")
      (node (ref "31") (pin "1") (pinfunction "1_1") (pintype "passive"))
    )
    (net (code "84") (name "/SERVICE_RXD") (class "Default")
      (node (ref "29") (pin "1") (pinfunction "1_1") (pintype "passive"))
    )
    (net (code "85") (name "/SERVICE_TXD") (class "Default")
      (node (ref "30") (pin "1") (pinfunction "1_1") (pintype "passive"))
    )
    (net (code "86") (name "/SW2") (class "Default")
      (node (ref "R53") (pin "2") (pinfunction "2_2") (pintype "passive"))
      (node (ref "SW2") (pin "2") (pinfunction "2_2") (pintype "passive"))
      (node (ref "SW2") (pin "4") (pinfunction "4_4") (pintype "passive"))
    )
    (net (code "87") (name "/SW3") (class "Default")
      (node (ref "R54") (pin "2") (pinfunction "2_2") (pintype "passive"))
      (node (ref "SW3") (pin "2") (pinfunction "2_2") (pintype "passive"))
      (node (ref "SW3") (pin "4") (pinfunction "4_4") (pintype "passive"))
    )
    (net (code "88") (name "/SWCLK") (class "Default")
      (node (ref "6") (pin "1") (pinfunction "1_1") (pintype "passive"))
      (node (ref "H4") (pin "3") (pinfunction "3_3") (pintype "passive"))
    )
    (net (code "89") (name "/SWDIO") (class "Default")
      (node (ref "7") (pin "1") (pinfunction "1_1") (pintype "passive"))
      (node (ref "H4") (pin "1") (pinfunction "1_1") (pintype "passive"))
    )
    (net (code "90") (name "/SWD_EN") (class "Default")
      (node (ref "23") (pin "1") (pinfunction "1_1") (pintype "passive"))
    )
    (net (code "91") (name "/SWO") (class "Default")
      (node (ref "8") (pin "1") (pinfunction "1_1") (pintype "passive"))
      (node (ref "H4") (pin "4") (pinfunction "4_4") (pintype "passive"))
    )
    (net (code "92") (name "/SYSRST_N") (class "Default")
      (node (ref "5") (pin "1") (pinfunction "1_1") (pintype "passive"))
      (node (ref "C37") (pin "2") (pinfunction "2_2") (pintype "passive"))
      (node (ref "H1") (pin "1") (pinfunction "1_1") (pintype "passive"))
      (node (ref "R8") (pin "2") (pinfunction "2_2") (pintype "passive"))
      (node (ref "SW1") (pin "1") (pinfunction "1_1") (pintype "passive"))
      (node (ref "SW1") (pin "2") (pinfunction "2_2") (pintype "passive"))
    )
    (net (code "93") (name "/TEST_IN") (class "Default")
      (node (ref "9") (pin "1") (pinfunction "1_1") (pintype "passive"))
    )
    (net (code "94") (name "/WAKEUP") (class "Default")
      (node (ref "1") (pin "1") (pinfunction "1_1") (pintype "passive"))
      (node (ref "H3") (pin "4") (pinfunction "4_4") (pintype "passive"))
    )
    (net (code "95") (name "3V3") (class "Default")
      (node (ref "19") (pin "1") (pinfunction "1_1") (pintype "passive"))
      (node (ref "D1") (pin "4") (pinfunction "A_4") (pintype "passive"))
      (node (ref "D2") (pin "4") (pinfunction "A_4") (pintype "passive"))
      (node (ref "D3") (pin "4") (pinfunction "A_4") (pintype "passive"))
      (node (ref "D4") (pin "4") (pinfunction "A_4") (pintype "passive"))
      (node (ref "D5") (pin "4") (pinfunction "A_4") (pintype "passive"))
      (node (ref "D6") (pin "4") (pinfunction "A_4") (pintype "passive"))
      (node (ref "D9") (pin "1") (pinfunction "A1_1") (pintype "passive"))
      (node (ref "H3") (pin "3") (pinfunction "3_3") (pintype "passive"))
      (node (ref "J2") (pin "2") (pinfunction "2_2") (pintype "passive"))
      (node (ref "J3") (pin "3") (pinfunction "3_3") (pintype "passive"))
      (node (ref "R53") (pin "1") (pinfunction "1_1") (pintype "passive"))
      (node (ref "R54") (pin "1") (pinfunction "1_1") (pintype "passive"))
      (node (ref "R6") (pin "1") (pinfunction "1_1") (pintype "passive"))
      (node (ref "R8") (pin "1") (pinfunction "1_1") (pintype "passive"))
    )
    (net (code "96") (name "3V3_RTC") (class "Default")
      (node (ref "24") (pin "1") (pinfunction "1_1") (pintype "passive"))
      (node (ref "J3") (pin "2") (pinfunction "2_2") (pintype "passive"))
    )
    (net (code "97") (name "5V") (class "Default")
      (node (ref "C24") (pin "2") (pinfunction "2_2") (pintype "passive"))
      (node (ref "H3") (pin "1") (pinfunction "1_1") (pintype "passive"))
      (node (ref "J5") (pin "1") (pinfunction "1_1") (pintype "passive"))
      (node (ref "Q1") (pin "4") (pinfunction "D2_4") (pintype "passive"))
      (node (ref "Q2") (pin "2") (pinfunction "S_2") (pintype "passive"))
      (node (ref "Q3") (pin "4") (pinfunction "E2_4") (pintype "passive"))
      (node (ref "R60") (pin "1") (pinfunction "1_1") (pintype "passive"))
    )
    (net (code "98") (name "GND") (class "Default")
      (node (ref "21") (pin "1") (pinfunction "1_1") (pintype "passive"))
      (node (ref "36") (pin "1") (pinfunction "1_1") (pintype "passive"))
      (node (ref "37") (pin "1") (pinfunction "1_1") (pintype "passive"))
      (node (ref "38") (pin "1") (pinfunction "1_1") (pintype "passive"))
      (node (ref "B1") (pin "2") (pinfunction "-_2") (pintype "passive"))
      (node (ref "C24") (pin "1") (pinfunction "1_1") (pintype "passive"))
      (node (ref "C25") (pin "1") (pinfunction "1_1") (pintype "passive"))
      (node (ref "C27") (pin "1") (pinfunction "1_1") (pintype "passive"))
      (node (ref "C37") (pin "1") (pinfunction "1_1") (pintype "passive"))
      (node (ref "C96") (pin "1") (pinfunction "1_1") (pintype "passive"))
      (node (ref "C97") (pin "1") (pinfunction "1_1") (pintype "passive"))
      (node (ref "D7") (pin "1") (pinfunction "K_1") (pintype "passive"))
      (node (ref "GND") (pin "1") (pinfunction "1_1") (pintype "passive"))
      (node (ref "H1") (pin "2") (pinfunction "2_2") (pintype "passive"))
      (node (ref "H2") (pin "2") (pinfunction "2_2") (pintype "passive"))
      (node (ref "H3") (pin "2") (pinfunction "2_2") (pintype "passive"))
      (node (ref "H4") (pin "2") (pinfunction "2_2") (pintype "passive"))
      (node (ref "J5") (pin "2") (pinfunction "2_2") (pintype "passive"))
      (node (ref "R5") (pin "2") (pinfunction "2_2") (pintype "passive"))
      (node (ref "R56") (pin "2") (pinfunction "2_2") (pintype "passive"))
      (node (ref "R57") (pin "2") (pinfunction "2_2") (pintype "passive"))
      (node (ref "R61") (pin "2") (pinfunction "2_2") (pintype "passive"))
      (node (ref "SW1") (pin "3") (pinfunction "3_3") (pintype "passive"))
      (node (ref "SW1") (pin "4") (pinfunction "4_4") (pintype "passive"))
      (node (ref "SW2") (pin "1") (pinfunction "1_1") (pintype "passive"))
      (node (ref "SW2") (pin "3") (pinfunction "3_3") (pintype "passive"))
      (node (ref "SW3") (pin "1") (pinfunction "1_1") (pintype "passive"))
      (node (ref "SW3") (pin "3") (pinfunction "3_3") (pintype "passive"))
      (node (ref "U8") (pin "1") (pinfunction "GND_1") (pintype "passive"))
      (node (ref "U8") (pin "4") (pinfunction "~{ON}_4") (pintype "passive"))
      (node (ref "U8") (pin "9") (pinfunction "EPAD_9") (pintype "passive"))
      (node (ref "U9") (pin "2") (pinfunction "GND_2") (pintype "passive"))
    )
    (net (code "99") (name "Net-(B1-+)") (class "Default")
      (node (ref "B1") (pin "1") (pinfunction "+_1") (pintype "passive"))
      (node (ref "R63") (pin "2") (pinfunction "2_2") (pintype "passive"))
    )
    (net (code "100") (name "Net-(C26-Pad2)") (class "Default")
      (node (ref "C26") (pin "2") (pinfunction "2_2") (pintype "passive"))
      (node (ref "C27") (pin "2") (pinfunction "2_2") (pintype "passive"))
      (node (ref "J2") (pin "1") (pinfunction "1_1") (pintype "passive"))
      (node (ref "L9") (pin "2") (pinfunction "2_2") (pintype "passive"))
      (node (ref "R4") (pin "1") (pinfunction "1_1") (pintype "passive"))
    )
    (net (code "101") (name "Net-(C95-Pad1)") (class "Default")
      (node (ref "C95") (pin "1") (pinfunction "1_1") (pintype "passive"))
      (node (ref "R61") (pin "1") (pinfunction "1_1") (pintype "passive"))
    )
    (net (code "102") (name "Net-(D1-B)") (class "Default")
      (node (ref "D1") (pin "3") (pinfunction "B_3") (pintype "passive"))
      (node (ref "RP3") (pin "1") (pinfunction "1_1") (pintype "passive"))
    )
    (net (code "103") (name "Net-(D1-G)") (class "Default")
      (node (ref "D1") (pin "2") (pinfunction "G_2") (pintype "passive"))
      (node (ref "RP2") (pin "1") (pinfunction "1_1") (pintype "passive"))
    )
    (net (code "104") (name "Net-(D1-R)") (class "Default")
      (node (ref "D1") (pin "1") (pinfunction "R_1") (pintype "passive"))
      (node (ref "RP1") (pin "1") (pinfunction "1_1") (pintype "passive"))
    )
    (net (code "105") (name "Net-(D2-B)") (class "Default")
      (node (ref "D2") (pin "3") (pinfunction "B_3") (pintype "passive"))
      (node (ref "RP3") (pin "3") (pinfunction "3_3") (pintype "passive"))
    )
    (net (code "106") (name "Net-(D2-G)") (class "Default")
      (node (ref "D2") (pin "2") (pinfunction "G_2") (pintype "passive"))
      (node (ref "RP2") (pin "3") (pinfunction "3_3") (pintype "passive"))
    )
    (net (code "107") (name "Net-(D2-R)") (class "Default")
      (node (ref "D2") (pin "1") (pinfunction "R_1") (pintype "passive"))
      (node (ref "RP1") (pin "3") (pinfunction "3_3") (pintype "passive"))
    )
    (net (code "108") (name "Net-(D3-B)") (class "Default")
      (node (ref "D3") (pin "3") (pinfunction "B_3") (pintype "passive"))
      (node (ref "RP3") (pin "5") (pinfunction "5_5") (pintype "passive"))
    )
    (net (code "109") (name "Net-(D3-G)") (class "Default")
      (node (ref "D3") (pin "2") (pinfunction "G_2") (pintype "passive"))
      (node (ref "RP2") (pin "5") (pinfunction "5_5") (pintype "passive"))
    )
    (net (code "110") (name "Net-(D3-R)") (class "Default")
      (node (ref "D3") (pin "1") (pinfunction "R_1") (pintype "passive"))
      (node (ref "RP1") (pin "5") (pinfunction "5_5") (pintype "passive"))
    )
    (net (code "111") (name "Net-(D4-B)") (class "Default")
      (node (ref "D4") (pin "3") (pinfunction "B_3") (pintype "passive"))
      (node (ref "RP3") (pin "7") (pinfunction "7_7") (pintype "passive"))
    )
    (net (code "112") (name "Net-(D4-G)") (class "Default")
      (node (ref "D4") (pin "2") (pinfunction "G_2") (pintype "passive"))
      (node (ref "RP2") (pin "7") (pinfunction "7_7") (pintype "passive"))
    )
    (net (code "113") (name "Net-(D4-R)") (class "Default")
      (node (ref "D4") (pin "1") (pinfunction "R_1") (pintype "passive"))
      (node (ref "RP1") (pin "7") (pinfunction "7_7") (pintype "passive"))
    )
    (net (code "114") (name "Net-(D5-B)") (class "Default")
      (node (ref "D5") (pin "3") (pinfunction "B_3") (pintype "passive"))
      (node (ref "R16") (pin "2") (pinfunction "2_2") (pintype "passive"))
    )
    (net (code "115") (name "Net-(D5-G)") (class "Default")
      (node (ref "D5") (pin "2") (pinfunction "G_2") (pintype "passive"))
      (node (ref "R15") (pin "1") (pinfunction "1_1") (pintype "passive"))
    )
    (net (code "116") (name "Net-(D5-R)") (class "Default")
      (node (ref "D5") (pin "1") (pinfunction "R_1") (pintype "passive"))
      (node (ref "R14") (pin "1") (pinfunction "1_1") (pintype "passive"))
    )
    (net (code "117") (name "Net-(D6-B)") (class "Default")
      (node (ref "D6") (pin "3") (pinfunction "B_3") (pintype "passive"))
      (node (ref "R19") (pin "2") (pinfunction "2_2") (pintype "passive"))
    )
    (net (code "118") (name "Net-(D6-G)") (class "Default")
      (node (ref "D6") (pin "2") (pinfunction "G_2") (pintype "passive"))
      (node (ref "R18") (pin "1") (pinfunction "1_1") (pintype "passive"))
    )
    (net (code "119") (name "Net-(D6-R)") (class "Default")
      (node (ref "D6") (pin "1") (pinfunction "R_1") (pintype "passive"))
      (node (ref "R17") (pin "1") (pinfunction "1_1") (pintype "passive"))
    )
    (net (code "120") (name "Net-(D7-A)") (class "Default")
      (node (ref "D7") (pin "2") (pinfunction "A_2") (pintype "passive"))
      (node (ref "R6") (pin "2") (pinfunction "2_2") (pintype "passive"))
    )
    (net (code "121") (name "Net-(D9A-K)") (class "Default")
      (node (ref "C97") (pin "2") (pinfunction "2_2") (pintype "passive"))
      (node (ref "D9") (pin "3") (pinfunction "K_3") (pintype "passive"))
      (node (ref "J3") (pin "1") (pinfunction "1_1") (pintype "passive"))
    )
    (net (code "122") (name "Net-(D9B-A2)") (class "Default")
      (node (ref "D9") (pin "2") (pinfunction "A2_2") (pintype "passive"))
      (node (ref "R63") (pin "1") (pinfunction "1_1") (pintype "passive"))
    )
    (net (code "123") (name "Net-(Q1A-D1)") (class "Default")
      (node (ref "Q1") (pin "6") (pinfunction "D1_6") (pintype "passive"))
      (node (ref "R3") (pin "1") (pinfunction "1_1") (pintype "passive"))
      (node (ref "U8") (pin "7") (pinfunction "SENSE_7") (pintype "passive"))
    )
    (net (code "124") (name "Net-(Q1A-G1)") (class "Default")
      (node (ref "Q1") (pin "1") (pinfunction "G1_1") (pintype "passive"))
      (node (ref "U8") (pin "6") (pinfunction "GATE_6") (pintype "passive"))
    )
    (net (code "125") (name "Net-(Q1A-S1)") (class "Default")
      (node (ref "C25") (pin "2") (pinfunction "2_2") (pintype "passive"))
      (node (ref "Q1") (pin "5") (pinfunction "S1_5") (pintype "passive"))
      (node (ref "R40") (pin "3") (pinfunction "3_3") (pintype "passive"))
      (node (ref "U8") (pin "3") (pinfunction "OUT_3") (pintype "passive"))
      (node (ref "U9") (pin "4") (pinfunction "VIN_4") (pintype "passive"))
    )
    (net (code "126") (name "Net-(Q1B-G2)") (class "Default")
      (node (ref "Q1") (pin "3") (pinfunction "G2_3") (pintype "passive"))
      (node (ref "U8") (pin "2") (pinfunction "GATEP_2") (pintype "passive"))
    )
    (net (code "127") (name "Net-(Q1B-S2)") (class "Default")
      (node (ref "Q1") (pin "2") (pinfunction "S2_2") (pintype "passive"))
      (node (ref "R3") (pin "2") (pinfunction "2_2") (pintype "passive"))
      (node (ref "U8") (pin "8") (pinfunction "IN_8") (pintype "passive"))
    )
    (net (code "128") (name "Net-(Q2-G)") (class "Default")
      (node (ref "Q2") (pin "1") (pinfunction "G_1") (pintype "passive"))
      (node (ref "Q3") (pin "3") (pinfunction "C2_3") (pintype "passive"))
      (node (ref "R57") (pin "1") (pinfunction "1_1") (pintype "passive"))
    )
    (net (code "129") (name "Net-(Q3A-B1)") (class "Default")
      (node (ref "Q3") (pin "2") (pinfunction "B1_2") (pintype "passive"))
      (node (ref "Q3") (pin "5") (pinfunction "B2_5") (pintype "passive"))
      (node (ref "Q3") (pin "6") (pinfunction "C1_6") (pintype "passive"))
      (node (ref "R56") (pin "1") (pinfunction "1_1") (pintype "passive"))
    )
    (net (code "130") (name "Net-(Q3A-E1)") (class "Default")
      (node (ref "C96") (pin "2") (pinfunction "2_2") (pintype "passive"))
      (node (ref "Q3") (pin "1") (pinfunction "E1_1") (pintype "passive"))
      (node (ref "R62") (pin "2") (pinfunction "2_2") (pintype "passive"))
    )
    (net (code "131") (name "Net-(U9-EN)") (class "Default")
      (node (ref "R40") (pin "2") (pinfunction "2_2") (pintype "passive"))
      (node (ref "U9") (pin "1") (pinfunction "EN_1") (pintype "passive"))
    )
    (net (code "132") (name "Net-(U9-FB)") (class "Default")
      (node (ref "C26") (pin "1") (pinfunction "1_1") (pintype "passive"))
      (node (ref "R4") (pin "2") (pinfunction "2_2") (pintype "passive"))
      (node (ref "R5") (pin "1") (pinfunction "1_1") (pintype "passive"))
      (node (ref "U9") (pin "5") (pinfunction "FB_5") (pintype "passive"))
    )
    (net (code "133") (name "Net-(U9-SW)") (class "Default")
      (node (ref "L9") (pin "1") (pinfunction "1_1") (pintype "passive"))
      (node (ref "U9") (pin "3") (pinfunction "SW_3") (pintype "passive"))
    )
    (net (code "134") (name "VBUS") (class "Default")
      (node (ref "20") (pin "1") (pinfunction "1_1") (pintype "passive"))
      (node (ref "C95") (pin "2") (pinfunction "2_2") (pintype "passive"))
      (node (ref "Q2") (pin "3") (pinfunction "D_3") (pintype "passive"))
      (node (ref "R60") (pin "2") (pinfunction "2_2") (pintype "passive"))
      (node (ref "R62") (pin "1") (pinfunction "1_1") (pintype "passive"))
    )
    (net (code "135") (name "unconnected-(J5-Pad3)") (class "Default")
      (node (ref "J5") (pin "3") (pinfunction "3_3") (pintype "passive"))
    )
    (net (code "136") (name "unconnected-(U8-~{PWRGD}-Pad5)") (class "Default")
      (node (ref "U8") (pin "5") (pinfunction "~{PWRGD}_5") (pintype "passive+no_connect"))
    )
  )
)
